# LMR14050_mod.net
KiCad netlist of a schematic drawn in Altium Designer
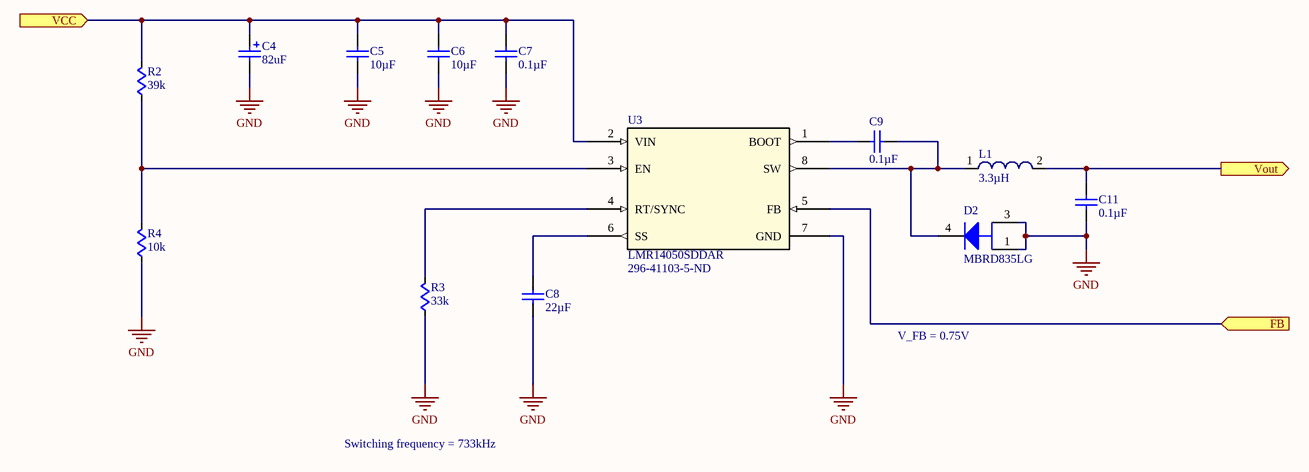
[diagram p0: LMR14050_mod.SchDoc]

(export (version "E")
  (design (tool "Eeschema 10.0.6"))
  (components
    (comp (ref "C4")
      (value "82uF")
      (footprint "CAP_EEFK_D8")
      (description "Polarized Capacitor (Surface Mount)")
      (fields (field (name "MANUFACTURER_PART_NUMBER") "EEEFK1V680XP"))
      (libsource (lib "AEVC-lib") (part "EEEFK1V680XP"))
    )
    (comp (ref "C5")
      (value "10µF")
      (footprint "C0805")
      (description "capacitor")
      (fields (field (name "Comment") "Cap"))
      (libsource (lib "ChipComponents") (part "Cap"))
    )
    (comp (ref "C6")
      (value "10µF")
      (footprint "C0805")
      (description "capacitor")
      (fields (field (name "Comment") "Cap"))
      (libsource (lib "ChipComponents") (part "Cap"))
    )
    (comp (ref "C7")
      (value "0.1µF")
      (footprint "C0805")
      (description "capacitor")
      (fields (field (name "Comment") "Cap"))
      (libsource (lib "ChipComponents") (part "Cap"))
    )
    (comp (ref "C8")
      (value "22µF")
      (footprint "C0805")
      (description "capacitor")
      (fields (field (name "Comment") "Cap"))
      (libsource (lib "ChipComponents") (part "Cap"))
    )
    (comp (ref "C9")
      (value "0.1µF")
      (footprint "C0805")
      (description "capacitor")
      (fields (field (name "Comment") "Cap"))
      (libsource (lib "ChipComponents") (part "Cap"))
    )
    (comp (ref "C11")
      (value "0.1µF")
      (footprint "C0805")
      (description "capacitor")
      (fields (field (name "Comment") "Cap"))
      (libsource (lib "ChipComponents") (part "Cap"))
    )
    (comp (ref "D2")
      (value "MBRD835LG")
      (footprint "ONSC-DPAK-3-369C-01_V")
      (description "SWITCHMODE(TM) Power Rectifier, 3-Pin DPAK, Pb-Free, Tube")
      (fields (field (name "MANUFACTURER") "On Semiconductor"))
      (libsource (lib "Altium Content Vault") (part "ONSC-D-A1A3K4-3_A"))
    )
    (comp (ref "L1")
      (value "3.3µH")
      (footprint "IHLP-2525C7")
      (description "Inductor")
      (fields (field (name "Comment") "Ind"))
      (libsource (lib "AEVC-bodyBoard") (part "Ind"))
    )
    (comp (ref "R2")
      (value "39k")
      (footprint "R0805")
      (description "resistor")
      (fields (field (name "Comment") "Res"))
      (libsource (lib "ChipComponents") (part "Res"))
    )
    (comp (ref "R3")
      (value "33k")
      (footprint "R0805")
      (description "resistor")
      (fields (field (name "Comment") "Res"))
      (libsource (lib "ChipComponents") (part "Res"))
    )
    (comp (ref "R4")
      (value "10k")
      (footprint "R0805")
      (description "resistor")
      (fields (field (name "Comment") "Res"))
      (libsource (lib "ChipComponents") (part "Res"))
    )
    (comp (ref "U3")
      (value "LMR14050SDDAR")
      (footprint "DDA8")
      (description "dc-dc converter")
      (fields (field (name "SUPPLIER PART NUMBER 1") "296-41103-5-ND"))
      (libsource (lib "AEVC-lib") (part "LMR14050SDDAR"))
    )
  )
  (nets
    (net (code "1") (name "/FB") (class "Default")
      (node (ref "U3") (pin "5") (pinfunction "FB_5") (pintype "input"))
    )
    (net (code "2") (name "/VCC") (class "Default")
      (node (ref "C4") (pin "1") (pinfunction "1_1") (pintype "passive"))
      (node (ref "C5") (pin "2") (pinfunction "2_2") (pintype "passive"))
      (node (ref "C6") (pin "2") (pinfunction "2_2") (pintype "passive"))
      (node (ref "C7") (pin "2") (pinfunction "2_2") (pintype "passive"))
      (node (ref "R2") (pin "2") (pinfunction "2_2") (pintype "passive"))
      (node (ref "U3") (pin "2") (pinfunction "VIN_2") (pintype "input"))
    )
    (net (code "3") (name "/Vout") (class "Default")
      (node (ref "C11") (pin "2") (pinfunction "2_2") (pintype "passive"))
      (node (ref "L1") (pin "2") (pinfunction "2_2") (pintype "passive"))
    )
    (net (code "4") (name "GND") (class "Default")
      (node (ref "C11") (pin "1") (pinfunction "1_1") (pintype "passive"))
      (node (ref "C4") (pin "2") (pinfunction "2_2") (pintype "passive"))
      (node (ref "C5") (pin "1") (pinfunction "1_1") (pintype "passive"))
      (node (ref "C6") (pin "1") (pinfunction "1_1") (pintype "passive"))
      (node (ref "C7") (pin "1") (pinfunction "1_1") (pintype "passive"))
      (node (ref "C8") (pin "1") (pinfunction "1_1") (pintype "passive"))
      (node (ref "D2") (pin "1") (pinfunction "A_1") (pintype "passive"))
      (node (ref "D2") (pin "3") (pinfunction "A_3") (pintype "passive"))
      (node (ref "R3") (pin "1") (pinfunction "1_1") (pintype "passive"))
      (node (ref "R4") (pin "1") (pinfunction "1_1") (pintype "passive"))
      (node (ref "U3") (pin "7") (pinfunction "GND_7") (pintype "power_in"))
    )
    (net (code "5") (name "Net-(D2-K)") (class "Default")
      (node (ref "C9") (pin "1") (pinfunction "1_1") (pintype "passive"))
      (node (ref "D2") (pin "4") (pinfunction "K_4") (pintype "passive"))
      (node (ref "L1") (pin "1") (pinfunction "1_1") (pintype "passive"))
      (node (ref "U3") (pin "8") (pinfunction "SW_8") (pintype "output"))
    )
    (net (code "6") (name "Net-(U3-BOOT)") (class "Default")
      (node (ref "C9") (pin "2") (pinfunction "2_2") (pintype "passive"))
      (node (ref "U3") (pin "1") (pinfunction "BOOT_1") (pintype "output"))
    )
    (net (code "7") (name "Net-(U3-EN)") (class "Default")
      (node (ref "R2") (pin "1") (pinfunction "1_1") (pintype "passive"))
      (node (ref "R4") (pin "2") (pinfunction "2_2") (pintype "passive"))
      (node (ref "U3") (pin "3") (pinfunction "EN_3") (pintype "input"))
    )
    (net (code "8") (name "Net-(U3-RT{slash}SYNC)") (class "Default")
      (node (ref "R3") (pin "2") (pinfunction "2_2") (pintype "passive"))
      (node (ref "U3") (pin "4") (pinfunction "RT/SYNC_4") (pintype "input"))
    )
    (net (code "9") (name "Net-(U3-SS)") (class "Default")
      (node (ref "C8") (pin "2") (pinfunction "2_2") (pintype "passive"))
      (node (ref "U3") (pin "6") (pinfunction "SS_6") (pintype "output"))
    )
  )
)
